# bladdnschbiela.net
KiCad netlist of a schematic drawn in EAGLE
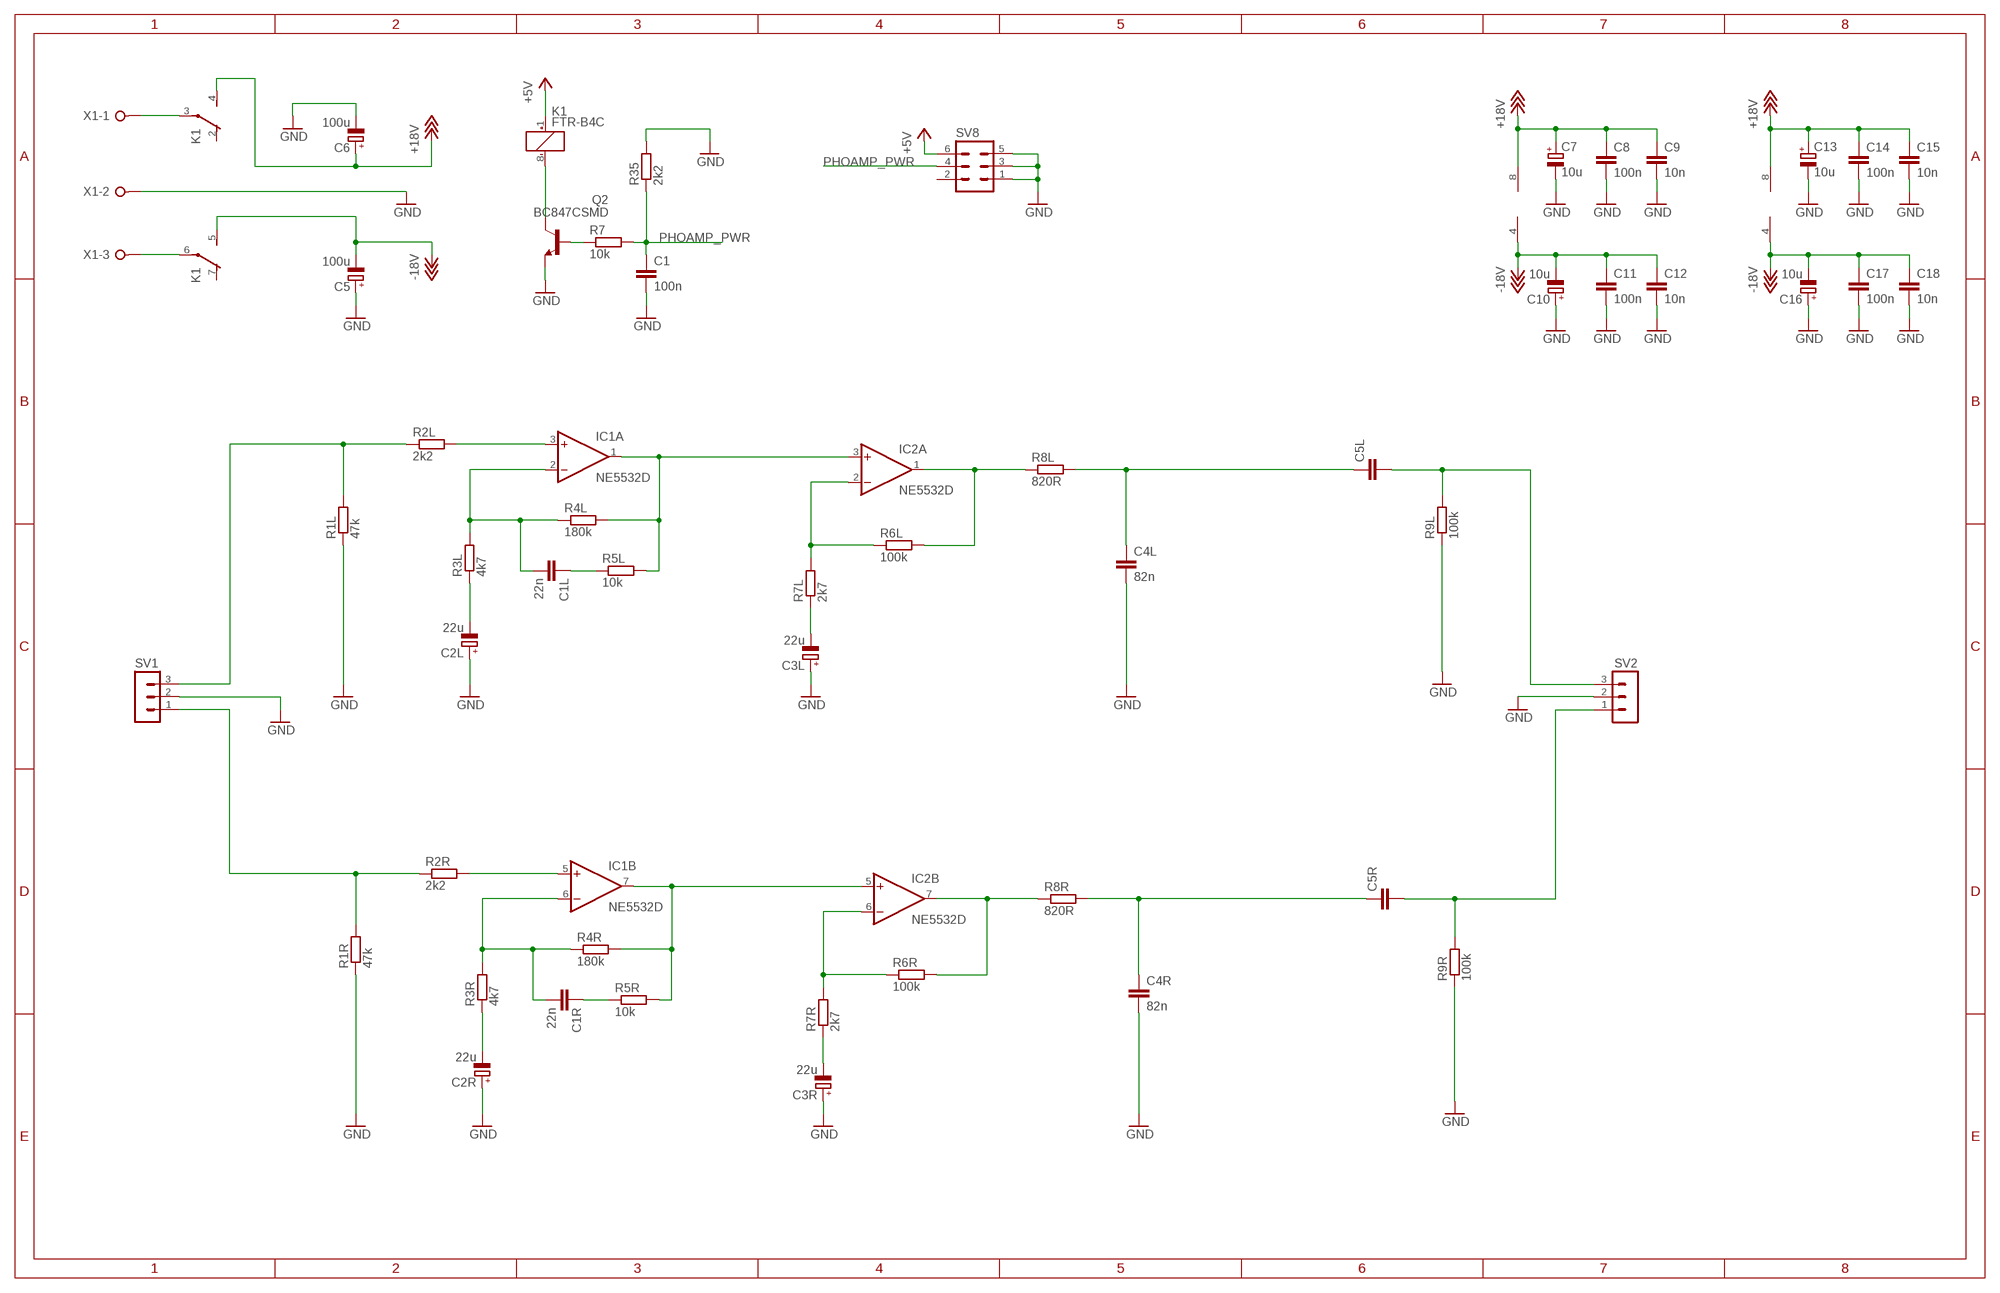
[diagram p0: schematic, sheet 1]

(export (version "E")
  (design (tool "Eeschema 10.0.6"))
  (components
    (comp (ref "C1")
      (value "100n")
      (footprint "eagle-import:C0603")
      (libsource (lib "eagle-import") (part "C-EUC0603"))
    )
    (comp (ref "C1L")
      (value "22n")
      (footprint "eagle-import:C1206")
      (libsource (lib "eagle-import") (part "C-EUC1206"))
    )
    (comp (ref "C1R")
      (value "22n")
      (footprint "eagle-import:C1206")
      (libsource (lib "eagle-import") (part "C-EUC1206"))
    )
    (comp (ref "C2L")
      (value "22u")
      (footprint "eagle-import:153CLV-0405")
      (libsource (lib "eagle-import") (part "CPOL-EU153CLV-0405"))
    )
    (comp (ref "C2R")
      (value "22u")
      (footprint "eagle-import:153CLV-0405")
      (libsource (lib "eagle-import") (part "CPOL-EU153CLV-0405"))
    )
    (comp (ref "C3L")
      (value "22u")
      (footprint "eagle-import:153CLV-0405")
      (libsource (lib "eagle-import") (part "CPOL-EU153CLV-0405"))
    )
    (comp (ref "C3R")
      (value "22u")
      (footprint "eagle-import:153CLV-0405")
      (libsource (lib "eagle-import") (part "CPOL-EU153CLV-0405"))
    )
    (comp (ref "C4L")
      (value "82n")
      (footprint "eagle-import:C1210")
      (libsource (lib "eagle-import") (part "C-EUC1210"))
    )
    (comp (ref "C4R")
      (value "82n")
      (footprint "eagle-import:C1210")
      (libsource (lib "eagle-import") (part "C-EUC1210"))
    )
    (comp (ref "C5")
      (value "100u")
      (footprint "eagle-import:153CLV-0605")
      (libsource (lib "eagle-import") (part "CPOL-EU153CLV-0605"))
    )
    (comp (ref "C5L")
      (value "C5/7.2/11")
      (footprint "eagle-import:C5B7.2_11")
      (libsource (lib "eagle-import") (part "C5/7.2/11"))
    )
    (comp (ref "C5R")
      (value "C5/7.2/11")
      (footprint "eagle-import:C5B7.2_11")
      (libsource (lib "eagle-import") (part "C5/7.2/11"))
    )
    (comp (ref "C6")
      (value "100u")
      (footprint "eagle-import:153CLV-0605")
      (libsource (lib "eagle-import") (part "CPOL-EU153CLV-0605"))
    )
    (comp (ref "C7")
      (value "10u")
      (footprint "eagle-import:153CLV-0405")
      (libsource (lib "eagle-import") (part "CPOL-EU153CLV-0405"))
    )
    (comp (ref "C8")
      (value "100n")
      (footprint "eagle-import:C0805")
      (libsource (lib "eagle-import") (part "C-EUC0805"))
    )
    (comp (ref "C9")
      (value "10n")
      (footprint "eagle-import:C0805")
      (libsource (lib "eagle-import") (part "C-EUC0805"))
    )
    (comp (ref "C10")
      (value "10u")
      (footprint "eagle-import:153CLV-0405")
      (libsource (lib "eagle-import") (part "CPOL-EU153CLV-0405"))
    )
    (comp (ref "C11")
      (value "100n")
      (footprint "eagle-import:C0805")
      (libsource (lib "eagle-import") (part "C-EUC0805"))
    )
    (comp (ref "C12")
      (value "10n")
      (footprint "eagle-import:C0805")
      (libsource (lib "eagle-import") (part "C-EUC0805"))
    )
    (comp (ref "C13")
      (value "10u")
      (footprint "eagle-import:153CLV-0405")
      (libsource (lib "eagle-import") (part "CPOL-EU153CLV-0405"))
    )
    (comp (ref "C14")
      (value "100n")
      (footprint "eagle-import:C0805")
      (libsource (lib "eagle-import") (part "C-EUC0805"))
    )
    (comp (ref "C15")
      (value "10n")
      (footprint "eagle-import:C0805")
      (libsource (lib "eagle-import") (part "C-EUC0805"))
    )
    (comp (ref "C16")
      (value "10u")
      (footprint "eagle-import:153CLV-0405")
      (libsource (lib "eagle-import") (part "CPOL-EU153CLV-0405"))
    )
    (comp (ref "C17")
      (value "100n")
      (footprint "eagle-import:C0805")
      (libsource (lib "eagle-import") (part "C-EUC0805"))
    )
    (comp (ref "C18")
      (value "10n")
      (footprint "eagle-import:C0805")
      (libsource (lib "eagle-import") (part "C-EUC0805"))
    )
    (comp (ref "IC1")
      (value "NE5532D")
      (footprint "eagle-import:SO08")
      (libsource (lib "eagle-import") (part "NE5532D"))
    )
    (comp (ref "IC2")
      (value "NE5532D")
      (footprint "eagle-import:SO08")
      (libsource (lib "eagle-import") (part "NE5532D"))
    )
    (comp (ref "K1")
      (value "FTR-B4C")
      (footprint "eagle-import:FTR-B4C")
      (libsource (lib "eagle-import") (part "FTR-B4C"))
    )
    (comp (ref "Q2")
      (value "BC847CSMD")
      (footprint "eagle-import:SOT23")
      (libsource (lib "eagle-import") (part "BC847SMDC"))
    )
    (comp (ref "R1L")
      (value "47k")
      (footprint "eagle-import:R0603")
      (libsource (lib "eagle-import") (part "R-EU_R0603"))
    )
    (comp (ref "R1R")
      (value "47k")
      (footprint "eagle-import:R0603")
      (libsource (lib "eagle-import") (part "R-EU_R0603"))
    )
    (comp (ref "R2L")
      (value "2k2")
      (footprint "eagle-import:R0603")
      (libsource (lib "eagle-import") (part "R-EU_R0603"))
    )
    (comp (ref "R2R")
      (value "2k2")
      (footprint "eagle-import:R0603")
      (libsource (lib "eagle-import") (part "R-EU_R0603"))
    )
    (comp (ref "R3L")
      (value "4k7")
      (footprint "eagle-import:R0603")
      (libsource (lib "eagle-import") (part "R-EU_R0603"))
    )
    (comp (ref "R3R")
      (value "4k7")
      (footprint "eagle-import:R0603")
      (libsource (lib "eagle-import") (part "R-EU_R0603"))
    )
    (comp (ref "R4L")
      (value "180k")
      (footprint "eagle-import:R0603")
      (libsource (lib "eagle-import") (part "R-EU_R0603"))
    )
    (comp (ref "R4R")
      (value "180k")
      (footprint "eagle-import:R0603")
      (libsource (lib "eagle-import") (part "R-EU_R0603"))
    )
    (comp (ref "R5L")
      (value "10k")
      (footprint "eagle-import:R0603")
      (libsource (lib "eagle-import") (part "R-EU_R0603"))
    )
    (comp (ref "R5R")
      (value "10k")
      (footprint "eagle-import:R0603")
      (libsource (lib "eagle-import") (part "R-EU_R0603"))
    )
    (comp (ref "R6L")
      (value "100k")
      (footprint "eagle-import:R0603")
      (libsource (lib "eagle-import") (part "R-EU_R0603"))
    )
    (comp (ref "R6R")
      (value "100k")
      (footprint "eagle-import:R0603")
      (libsource (lib "eagle-import") (part "R-EU_R0603"))
    )
    (comp (ref "R7")
      (value "10k")
      (footprint "eagle-import:R0603")
      (libsource (lib "eagle-import") (part "R-EU_R0603"))
    )
    (comp (ref "R7L")
      (value "2k7")
      (footprint "eagle-import:R0603")
      (libsource (lib "eagle-import") (part "R-EU_R0603"))
    )
    (comp (ref "R7R")
      (value "2k7")
      (footprint "eagle-import:R0603")
      (libsource (lib "eagle-import") (part "R-EU_R0603"))
    )
    (comp (ref "R8L")
      (value "820R")
      (footprint "eagle-import:R0603")
      (libsource (lib "eagle-import") (part "R-EU_R0603"))
    )
    (comp (ref "R8R")
      (value "820R")
      (footprint "eagle-import:R0603")
      (libsource (lib "eagle-import") (part "R-EU_R0603"))
    )
    (comp (ref "R9L")
      (value "100k")
      (footprint "eagle-import:R0603")
      (libsource (lib "eagle-import") (part "R-EU_R0603"))
    )
    (comp (ref "R9R")
      (value "100k")
      (footprint "eagle-import:R0603")
      (libsource (lib "eagle-import") (part "R-EU_R0603"))
    )
    (comp (ref "R35")
      (value "2k2")
      (footprint "eagle-import:R0603")
      (libsource (lib "eagle-import") (part "R-EU_R0603"))
    )
    (comp (ref "SV1")
      (value "MA03-1")
      (footprint "eagle-import:MA03-1")
      (libsource (lib "eagle-import") (part "MA03-1"))
    )
    (comp (ref "SV2")
      (value "MA03-1")
      (footprint "eagle-import:MA03-1")
      (libsource (lib "eagle-import") (part "MA03-1"))
    )
    (comp (ref "SV8")
      (value "MA03-2B")
      (footprint "eagle-import:MA03-2_BORDER")
      (libsource (lib "eagle-import") (part "MA03-2B"))
    )
    (comp (ref "X1")
      (value "W237-3E")
      (footprint "eagle-import:W237-3E")
      (libsource (lib "eagle-import") (part "W237-3E"))
    )
  )
  (nets
    (net (code "1") (name "+5V") (class "Default")
      (node (ref "K1") (pin "1") (pinfunction "+_1") (pintype "passive"))
      (node (ref "SV8") (pin "6") (pinfunction "6_6") (pintype "passive"))
    )
    (net (code "2") (name "+18V") (class "Default")
      (node (ref "C13") (pin "+") (pinfunction "+_+") (pintype "passive"))
      (node (ref "C14") (pin "1") (pinfunction "1_1") (pintype "passive"))
      (node (ref "C15") (pin "1") (pinfunction "1_1") (pintype "passive"))
      (node (ref "C6") (pin "+") (pinfunction "+_+") (pintype "passive"))
      (node (ref "C7") (pin "+") (pinfunction "+_+") (pintype "passive"))
      (node (ref "C8") (pin "1") (pinfunction "1_1") (pintype "passive"))
      (node (ref "C9") (pin "1") (pinfunction "1_1") (pintype "passive"))
      (node (ref "IC1") (pin "8") (pinfunction "V+_8") (pintype "power_in"))
      (node (ref "IC2") (pin "8") (pinfunction "V+_8") (pintype "power_in"))
      (node (ref "K1") (pin "4") (pinfunction "S_4") (pintype "passive"))
    )
    (net (code "3") (name "-18V") (class "Default")
      (node (ref "C10") (pin "-") (pinfunction "-_-") (pintype "passive"))
      (node (ref "C11") (pin "1") (pinfunction "1_1") (pintype "passive"))
      (node (ref "C12") (pin "1") (pinfunction "1_1") (pintype "passive"))
      (node (ref "C16") (pin "-") (pinfunction "-_-") (pintype "passive"))
      (node (ref "C17") (pin "1") (pinfunction "1_1") (pintype "passive"))
      (node (ref "C18") (pin "1") (pinfunction "1_1") (pintype "passive"))
      (node (ref "C5") (pin "-") (pinfunction "-_-") (pintype "passive"))
      (node (ref "IC1") (pin "4") (pinfunction "V-_4") (pintype "power_in"))
      (node (ref "IC2") (pin "4") (pinfunction "V-_4") (pintype "power_in"))
      (node (ref "K1") (pin "5") (pinfunction "S_5") (pintype "passive"))
    )
    (net (code "4") (name "/PHOAMP_PWR") (class "Default")
      (node (ref "C1") (pin "1") (pinfunction "1_1") (pintype "passive"))
      (node (ref "R35") (pin "1") (pinfunction "1_1") (pintype "passive"))
      (node (ref "R7") (pin "2") (pinfunction "2_2") (pintype "passive"))
      (node (ref "SV8") (pin "4") (pinfunction "4_4") (pintype "passive"))
    )
    (net (code "5") (name "GND") (class "Default")
      (node (ref "C1") (pin "2") (pinfunction "2_2") (pintype "passive"))
      (node (ref "C10") (pin "+") (pinfunction "+_+") (pintype "passive"))
      (node (ref "C11") (pin "2") (pinfunction "2_2") (pintype "passive"))
      (node (ref "C12") (pin "2") (pinfunction "2_2") (pintype "passive"))
      (node (ref "C13") (pin "-") (pinfunction "-_-") (pintype "passive"))
      (node (ref "C14") (pin "2") (pinfunction "2_2") (pintype "passive"))
      (node (ref "C15") (pin "2") (pinfunction "2_2") (pintype "passive"))
      (node (ref "C16") (pin "+") (pinfunction "+_+") (pintype "passive"))
      (node (ref "C17") (pin "2") (pinfunction "2_2") (pintype "passive"))
      (node (ref "C18") (pin "2") (pinfunction "2_2") (pintype "passive"))
      (node (ref "C2L") (pin "+") (pinfunction "+_+") (pintype "passive"))
      (node (ref "C2R") (pin "+") (pinfunction "+_+") (pintype "passive"))
      (node (ref "C3L") (pin "+") (pinfunction "+_+") (pintype "passive"))
      (node (ref "C3R") (pin "+") (pinfunction "+_+") (pintype "passive"))
      (node (ref "C4L") (pin "2") (pinfunction "2_2") (pintype "passive"))
      (node (ref "C4R") (pin "2") (pinfunction "2_2") (pintype "passive"))
      (node (ref "C5") (pin "+") (pinfunction "+_+") (pintype "passive"))
      (node (ref "C6") (pin "-") (pinfunction "-_-") (pintype "passive"))
      (node (ref "C7") (pin "-") (pinfunction "-_-") (pintype "passive"))
      (node (ref "C8") (pin "2") (pinfunction "2_2") (pintype "passive"))
      (node (ref "C9") (pin "2") (pinfunction "2_2") (pintype "passive"))
      (node (ref "Q2") (pin "2") (pinfunction "E_2") (pintype "passive"))
      (node (ref "R1L") (pin "1") (pinfunction "1_1") (pintype "passive"))
      (node (ref "R1R") (pin "1") (pinfunction "1_1") (pintype "passive"))
      (node (ref "R35") (pin "2") (pinfunction "2_2") (pintype "passive"))
      (node (ref "R9L") (pin "1") (pinfunction "1_1") (pintype "passive"))
      (node (ref "R9R") (pin "1") (pinfunction "1_1") (pintype "passive"))
      (node (ref "SV1") (pin "2") (pinfunction "2_2") (pintype "passive"))
      (node (ref "SV2") (pin "2") (pinfunction "2_2") (pintype "passive"))
      (node (ref "SV8") (pin "1") (pinfunction "1_1") (pintype "passive"))
      (node (ref "SV8") (pin "3") (pinfunction "3_3") (pintype "passive"))
      (node (ref "SV8") (pin "5") (pinfunction "5_5") (pintype "passive"))
      (node (ref "X1") (pin "2") (pinfunction "KL_2") (pintype "passive"))
    )
    (net (code "6") (name "Net-(C1L-Pad1)") (class "Default")
      (node (ref "C1L") (pin "1") (pinfunction "1_1") (pintype "passive"))
      (node (ref "R5L") (pin "1") (pinfunction "1_1") (pintype "passive"))
    )
    (net (code "7") (name "Net-(C1R-Pad1)") (class "Default")
      (node (ref "C1R") (pin "1") (pinfunction "1_1") (pintype "passive"))
      (node (ref "R5R") (pin "1") (pinfunction "1_1") (pintype "passive"))
    )
    (net (code "8") (name "Net-(C2L-Pad-)") (class "Default")
      (node (ref "C2L") (pin "-") (pinfunction "-_-") (pintype "passive"))
      (node (ref "R3L") (pin "1") (pinfunction "1_1") (pintype "passive"))
    )
    (net (code "9") (name "Net-(C2R-Pad-)") (class "Default")
      (node (ref "C2R") (pin "-") (pinfunction "-_-") (pintype "passive"))
      (node (ref "R3R") (pin "1") (pinfunction "1_1") (pintype "passive"))
    )
    (net (code "10") (name "Net-(C3L-Pad-)") (class "Default")
      (node (ref "C3L") (pin "-") (pinfunction "-_-") (pintype "passive"))
      (node (ref "R7L") (pin "1") (pinfunction "1_1") (pintype "passive"))
    )
    (net (code "11") (name "Net-(C3R-Pad-)") (class "Default")
      (node (ref "C3R") (pin "-") (pinfunction "-_-") (pintype "passive"))
      (node (ref "R7R") (pin "1") (pinfunction "1_1") (pintype "passive"))
    )
    (net (code "12") (name "Net-(C4L-Pad1)") (class "Default")
      (node (ref "C4L") (pin "1") (pinfunction "1_1") (pintype "passive"))
      (node (ref "C5L") (pin "1") (pinfunction "1_1") (pintype "passive"))
      (node (ref "R8L") (pin "2") (pinfunction "2_2") (pintype "passive"))
    )
    (net (code "13") (name "Net-(C4R-Pad1)") (class "Default")
      (node (ref "C4R") (pin "1") (pinfunction "1_1") (pintype "passive"))
      (node (ref "C5R") (pin "1") (pinfunction "1_1") (pintype "passive"))
      (node (ref "R8R") (pin "2") (pinfunction "2_2") (pintype "passive"))
    )
    (net (code "14") (name "Net-(C5L-Pad2)") (class "Default")
      (node (ref "C5L") (pin "2") (pinfunction "2_2") (pintype "passive"))
      (node (ref "R9L") (pin "2") (pinfunction "2_2") (pintype "passive"))
      (node (ref "SV2") (pin "3") (pinfunction "3_3") (pintype "passive"))
    )
    (net (code "15") (name "Net-(C5R-Pad2)") (class "Default")
      (node (ref "C5R") (pin "2") (pinfunction "2_2") (pintype "passive"))
      (node (ref "R9R") (pin "2") (pinfunction "2_2") (pintype "passive"))
      (node (ref "SV2") (pin "1") (pinfunction "1_1") (pintype "passive"))
    )
    (net (code "16") (name "Net-(IC1A-+IN)") (class "Default")
      (node (ref "IC1") (pin "3") (pinfunction "+IN_3") (pintype "input"))
      (node (ref "R2L") (pin "2") (pinfunction "2_2") (pintype "passive"))
    )
    (net (code "17") (name "Net-(IC1A--IN)") (class "Default")
      (node (ref "C1L") (pin "2") (pinfunction "2_2") (pintype "passive"))
      (node (ref "IC1") (pin "2") (pinfunction "-IN_2") (pintype "input"))
      (node (ref "R3L") (pin "2") (pinfunction "2_2") (pintype "passive"))
      (node (ref "R4L") (pin "1") (pinfunction "1_1") (pintype "passive"))
    )
    (net (code "18") (name "Net-(IC1A-OUT)") (class "Default")
      (node (ref "IC1") (pin "1") (pinfunction "OUT_1") (pintype "output"))
      (node (ref "IC2") (pin "3") (pinfunction "+IN_3") (pintype "input"))
      (node (ref "R4L") (pin "2") (pinfunction "2_2") (pintype "passive"))
      (node (ref "R5L") (pin "2") (pinfunction "2_2") (pintype "passive"))
    )
    (net (code "19") (name "Net-(IC1B-+IN)") (class "Default")
      (node (ref "IC1") (pin "5") (pinfunction "+IN_5") (pintype "input"))
      (node (ref "R2R") (pin "2") (pinfunction "2_2") (pintype "passive"))
    )
    (net (code "20") (name "Net-(IC1B--IN)") (class "Default")
      (node (ref "C1R") (pin "2") (pinfunction "2_2") (pintype "passive"))
      (node (ref "IC1") (pin "6") (pinfunction "-IN_6") (pintype "input"))
      (node (ref "R3R") (pin "2") (pinfunction "2_2") (pintype "passive"))
      (node (ref "R4R") (pin "1") (pinfunction "1_1") (pintype "passive"))
    )
    (net (code "21") (name "Net-(IC1B-OUT)") (class "Default")
      (node (ref "IC1") (pin "7") (pinfunction "OUT_7") (pintype "output"))
      (node (ref "IC2") (pin "5") (pinfunction "+IN_5") (pintype "input"))
      (node (ref "R4R") (pin "2") (pinfunction "2_2") (pintype "passive"))
      (node (ref "R5R") (pin "2") (pinfunction "2_2") (pintype "passive"))
    )
    (net (code "22") (name "Net-(IC2A--IN)") (class "Default")
      (node (ref "IC2") (pin "2") (pinfunction "-IN_2") (pintype "input"))
      (node (ref "R6L") (pin "1") (pinfunction "1_1") (pintype "passive"))
      (node (ref "R7L") (pin "2") (pinfunction "2_2") (pintype "passive"))
    )
    (net (code "23") (name "Net-(IC2A-OUT)") (class "Default")
      (node (ref "IC2") (pin "1") (pinfunction "OUT_1") (pintype "output"))
      (node (ref "R6L") (pin "2") (pinfunction "2_2") (pintype "passive"))
      (node (ref "R8L") (pin "1") (pinfunction "1_1") (pintype "passive"))
    )
    (net (code "24") (name "Net-(IC2B--IN)") (class "Default")
      (node (ref "IC2") (pin "6") (pinfunction "-IN_6") (pintype "input"))
      (node (ref "R6R") (pin "1") (pinfunction "1_1") (pintype "passive"))
      (node (ref "R7R") (pin "2") (pinfunction "2_2") (pintype "passive"))
    )
    (net (code "25") (name "Net-(IC2B-OUT)") (class "Default")
      (node (ref "IC2") (pin "7") (pinfunction "OUT_7") (pintype "output"))
      (node (ref "R6R") (pin "2") (pinfunction "2_2") (pintype "passive"))
      (node (ref "R8R") (pin "1") (pinfunction "1_1") (pintype "passive"))
    )
    (net (code "26") (name "Net-(K1A-P)") (class "Default")
      (node (ref "K1") (pin "3") (pinfunction "P_3") (pintype "passive"))
      (node (ref "X1") (pin "1") (pinfunction "KL_1") (pintype "passive"))
    )
    (net (code "27") (name "Net-(K1B-P)") (class "Default")
      (node (ref "K1") (pin "6") (pinfunction "P_6") (pintype "passive"))
      (node (ref "X1") (pin "3") (pinfunction "KL_3") (pintype "passive"))
    )
    (net (code "28") (name "Net-(K1C--)") (class "Default")
      (node (ref "K1") (pin "8") (pinfunction "-_8") (pintype "passive"))
      (node (ref "Q2") (pin "3") (pinfunction "C_3") (pintype "passive"))
    )
    (net (code "29") (name "Net-(Q2-B)") (class "Default")
      (node (ref "Q2") (pin "1") (pinfunction "B_1") (pintype "passive"))
      (node (ref "R7") (pin "1") (pinfunction "1_1") (pintype "passive"))
    )
    (net (code "30") (name "Net-(R1L-Pad2)") (class "Default")
      (node (ref "R1L") (pin "2") (pinfunction "2_2") (pintype "passive"))
      (node (ref "R2L") (pin "1") (pinfunction "1_1") (pintype "passive"))
      (node (ref "SV1") (pin "3") (pinfunction "3_3") (pintype "passive"))
    )
    (net (code "31") (name "Net-(R1R-Pad2)") (class "Default")
      (node (ref "R1R") (pin "2") (pinfunction "2_2") (pintype "passive"))
      (node (ref "R2R") (pin "1") (pinfunction "1_1") (pintype "passive"))
      (node (ref "SV1") (pin "1") (pinfunction "1_1") (pintype "passive"))
    )
    (net (code "32") (name "unconnected-(K1A-O-Pad2)") (class "Default")
      (node (ref "K1") (pin "2") (pinfunction "O_2") (pintype "passive"))
    )
    (net (code "33") (name "unconnected-(K1B-O-Pad7)") (class "Default")
      (node (ref "K1") (pin "7") (pinfunction "O_7") (pintype "passive"))
    )
    (net (code "34") (name "unconnected-(SV8-Pad2)") (class "Default")
      (node (ref "SV8") (pin "2") (pinfunction "2_2") (pintype "passive"))
    )
  )
)
